# Peripherals.net
KiCad netlist of a schematic drawn in Altium Designer
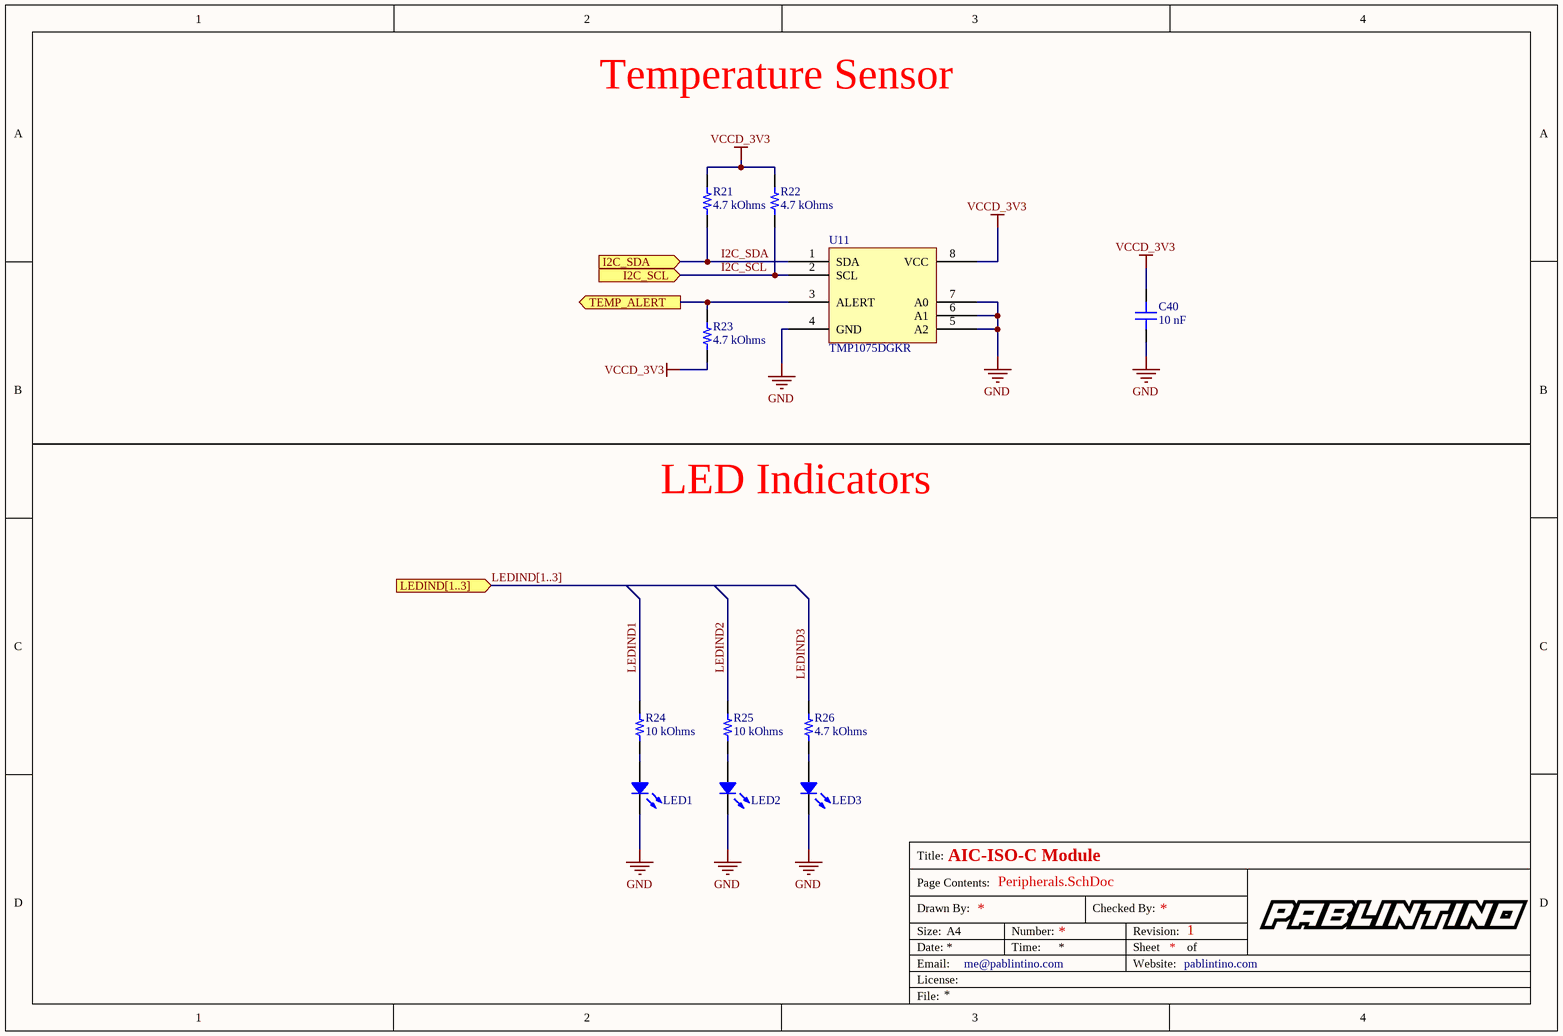
[diagram p0: Peripherals.SchDoc]

(export (version "E")
  (design (tool "Eeschema 10.0.6"))
  (components
    (comp (ref "C40")
      (value "10 nF")
      (footprint "CAP 0603_1608")
      (description "MLCC Ceramic 10 nF 16 V 5% Capacitor")
      (fields (field (name "PART NUMBER") "0603YC103JAT2A") (field (name "MANUFACTURER") "AVX"))
      (libsource (lib "Database_Libs") (part "Capacitor"))
    )
    (comp (ref "LED1")
      (value "APTD1608LZGCK")
      (footprint "LED 0603_1608 GREEN")
      (description "SMD Low Current Green LED")
      (fields (field (name "MANUFACTURER") "Kingbright"))
      (libsource (lib "Database_Libs") (part "LED"))
    )
    (comp (ref "LED2")
      (value "APTD1608LZGCK")
      (footprint "LED 0603_1608 GREEN")
      (description "SMD Low Current Green LED")
      (fields (field (name "MANUFACTURER") "Kingbright"))
      (libsource (lib "Database_Libs") (part "LED"))
    )
    (comp (ref "LED3")
      (value "APTD1608LSECK")
      (footprint "LED 0603_1608 RED")
      (description "SMD Low Current Red LED")
      (fields (field (name "MANUFACTURER") "Kingbright"))
      (libsource (lib "Database_Libs") (part "LED"))
    )
    (comp (ref "R21")
      (value "4.7 kOhms")
      (footprint "RES 0603_1608")
      (description "Thin Film Resistor 4.7 kOhms 1%")
      (fields (field (name "PART NUMBER") "CRCW06034K70FKEAC") (field (name "MANUFACTURER") "Vishay / Dale"))
      (libsource (lib "Database_Libs") (part "Resistor"))
    )
    (comp (ref "R22")
      (value "4.7 kOhms")
      (footprint "RES 0603_1608")
      (description "Thin Film Resistor 4.7 kOhms 1%")
      (fields (field (name "PART NUMBER") "CRCW06034K70FKEAC") (field (name "MANUFACTURER") "Vishay / Dale"))
      (libsource (lib "Database_Libs") (part "Resistor"))
    )
    (comp (ref "R23")
      (value "4.7 kOhms")
      (footprint "RES 0603_1608")
      (description "Thin Film Resistor 4.7 kOhms 1%")
      (fields (field (name "PART NUMBER") "CRCW06034K70FKEAC") (field (name "MANUFACTURER") "Vishay / Dale"))
      (libsource (lib "Database_Libs") (part "Resistor"))
    )
    (comp (ref "R24")
      (value "10 kOhms")
      (footprint "RES 0603_1608")
      (description "Thin Film Resistor 10 kOhms 1%")
      (fields (field (name "PART NUMBER") "CRCW060310K0FKEAC") (field (name "MANUFACTURER") "Vishay / Dale"))
      (libsource (lib "Database_Libs") (part "Resistor"))
    )
    (comp (ref "R25")
      (value "10 kOhms")
      (footprint "RES 0603_1608")
      (description "Thin Film Resistor 10 kOhms 1%")
      (fields (field (name "PART NUMBER") "CRCW060310K0FKEAC") (field (name "MANUFACTURER") "Vishay / Dale"))
      (libsource (lib "Database_Libs") (part "Resistor"))
    )
    (comp (ref "R26")
      (value "4.7 kOhms")
      (footprint "RES 0603_1608")
      (description "Thin Film Resistor 4.7 kOhms 1%")
      (fields (field (name "PART NUMBER") "CRCW06034K70FKEAC") (field (name "MANUFACTURER") "Vishay / Dale"))
      (libsource (lib "Database_Libs") (part "Resistor"))
    )
    (comp (ref "U11")
      (value "TMP1075DGKR")
      (footprint "TI VSSOP-8 DGK")
      (description "TMP1075 Temperature Sensor With I2C and SMBus Interface")
      (fields (field (name "MANUFACTURER") "Texas Instruments"))
      (libsource (lib "Database_Libs") (part "TMP1075"))
    )
  )
  (nets
    (net (code "1") (name "/I2C_SCL") (class "Default")
      (node (ref "R22") (pin "1") (pinfunction "1_1") (pintype "passive"))
      (node (ref "U11") (pin "2") (pinfunction "SCL_2") (pintype "passive"))
    )
    (net (code "2") (name "/I2C_SDA") (class "Default")
      (node (ref "R21") (pin "1") (pinfunction "1_1") (pintype "passive"))
      (node (ref "U11") (pin "1") (pinfunction "SDA_1") (pintype "passive"))
    )
    (net (code "3") (name "/LEDIND1") (class "Default")
      (node (ref "R24") (pin "1") (pinfunction "1_1") (pintype "passive"))
    )
    (net (code "4") (name "/LEDIND2") (class "Default")
      (node (ref "R25") (pin "1") (pinfunction "1_1") (pintype "passive"))
    )
    (net (code "5") (name "/LEDIND3") (class "Default")
      (node (ref "R26") (pin "1") (pinfunction "1_1") (pintype "passive"))
    )
    (net (code "7") (name "/TEMP_ALERT") (class "Default")
      (node (ref "R23") (pin "2") (pinfunction "2_2") (pintype "passive"))
      (node (ref "U11") (pin "3") (pinfunction "ALERT_3") (pintype "passive"))
    )
    (net (code "8") (name "GND") (class "Default")
      (node (ref "C40") (pin "2") (pinfunction "2_2") (pintype "passive"))
      (node (ref "LED1") (pin "2") (pinfunction "2_2") (pintype "passive"))
      (node (ref "LED2") (pin "2") (pinfunction "2_2") (pintype "passive"))
      (node (ref "LED3") (pin "2") (pinfunction "2_2") (pintype "passive"))
      (node (ref "U11") (pin "4") (pinfunction "GND_4") (pintype "passive"))
      (node (ref "U11") (pin "5") (pinfunction "A2_5") (pintype "passive"))
      (node (ref "U11") (pin "6") (pinfunction "A1_6") (pintype "passive"))
      (node (ref "U11") (pin "7") (pinfunction "A0_7") (pintype "passive"))
    )
    (net (code "9") (name "Net-(LED1-Pad1)") (class "Default")
      (node (ref "LED1") (pin "1") (pinfunction "1_1") (pintype "passive"))
      (node (ref "R24") (pin "2") (pinfunction "2_2") (pintype "passive"))
    )
    (net (code "10") (name "Net-(LED2-Pad1)") (class "Default")
      (node (ref "LED2") (pin "1") (pinfunction "1_1") (pintype "passive"))
      (node (ref "R25") (pin "2") (pinfunction "2_2") (pintype "passive"))
    )
    (net (code "11") (name "Net-(LED3-Pad1)") (class "Default")
      (node (ref "LED3") (pin "1") (pinfunction "1_1") (pintype "passive"))
      (node (ref "R26") (pin "2") (pinfunction "2_2") (pintype "passive"))
    )
    (net (code "12") (name "VCCD_3V3") (class "Default")
      (node (ref "C40") (pin "1") (pinfunction "1_1") (pintype "passive"))
      (node (ref "R21") (pin "2") (pinfunction "2_2") (pintype "passive"))
      (node (ref "R22") (pin "2") (pinfunction "2_2") (pintype "passive"))
      (node (ref "R23") (pin "1") (pinfunction "1_1") (pintype "passive"))
      (node (ref "U11") (pin "8") (pinfunction "VCC_8") (pintype "passive"))
    )
  )
)
